# Exp_Board_Printrboard_v0_1.net
KiCad netlist of a schematic drawn in EAGLE
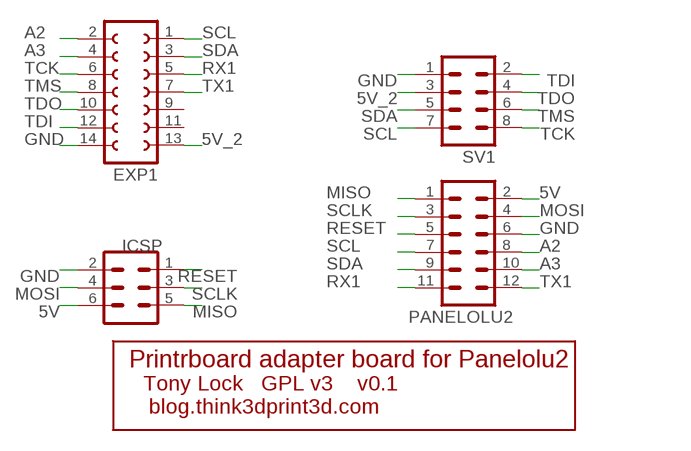
[diagram p0: schematic, sheet 1]

(export (version "E")
  (design (tool "Eeschema 10.0.6"))
  (components
    (comp (ref "EXP1")
      (value "FE07-2")
      (footprint "eagle-import:FE07-2")
      (libsource (lib "eagle-import") (part "FE07-2"))
    )
    (comp (ref "ICSP")
      (value "MA03-2")
      (footprint "eagle-import:MA03-2")
      (libsource (lib "eagle-import") (part "MA03-2"))
    )
    (comp (ref "PANELOLU2")
      (value "MA06-2_BACK")
      (footprint "eagle-import:MA06-2_BACK")
      (libsource (lib "eagle-import") (part "MA06-2_BACK"))
    )
    (comp (ref "SV1")
      (value "MA04-2")
      (footprint "eagle-import:MA04-2")
      (libsource (lib "eagle-import") (part "MA04-2"))
    )
  )
  (nets
    (net (code "1") (name "/5V") (class "Default")
      (node (ref "ICSP") (pin "6") (pinfunction "6_6") (pintype "passive"))
      (node (ref "PANELOLU2") (pin "2") (pinfunction "2_2") (pintype "passive"))
    )
    (net (code "2") (name "/5V_2") (class "Default")
      (node (ref "EXP1") (pin "13") (pinfunction "13_13") (pintype "passive"))
      (node (ref "SV1") (pin "3") (pinfunction "3_3") (pintype "passive"))
    )
    (net (code "3") (name "/A2") (class "Default")
      (node (ref "EXP1") (pin "2") (pinfunction "2_2") (pintype "passive"))
      (node (ref "PANELOLU2") (pin "8") (pinfunction "8_8") (pintype "passive"))
    )
    (net (code "4") (name "/A3") (class "Default")
      (node (ref "EXP1") (pin "4") (pinfunction "4_4") (pintype "passive"))
      (node (ref "PANELOLU2") (pin "10") (pinfunction "10_10") (pintype "passive"))
    )
    (net (code "5") (name "/GND") (class "Default")
      (node (ref "EXP1") (pin "14") (pinfunction "14_14") (pintype "passive"))
      (node (ref "ICSP") (pin "2") (pinfunction "2_2") (pintype "passive"))
      (node (ref "PANELOLU2") (pin "6") (pinfunction "6_6") (pintype "passive"))
      (node (ref "SV1") (pin "1") (pinfunction "1_1") (pintype "passive"))
    )
    (net (code "6") (name "/MISO") (class "Default")
      (node (ref "ICSP") (pin "5") (pinfunction "5_5") (pintype "passive"))
      (node (ref "PANELOLU2") (pin "1") (pinfunction "1_1") (pintype "passive"))
    )
    (net (code "7") (name "/MOSI") (class "Default")
      (node (ref "ICSP") (pin "4") (pinfunction "4_4") (pintype "passive"))
      (node (ref "PANELOLU2") (pin "4") (pinfunction "4_4") (pintype "passive"))
    )
    (net (code "8") (name "/RESET") (class "Default")
      (node (ref "ICSP") (pin "1") (pinfunction "1_1") (pintype "passive"))
      (node (ref "PANELOLU2") (pin "5") (pinfunction "5_5") (pintype "passive"))
    )
    (net (code "9") (name "/RX1") (class "Default")
      (node (ref "EXP1") (pin "5") (pinfunction "5_5") (pintype "passive"))
      (node (ref "PANELOLU2") (pin "11") (pinfunction "11_11") (pintype "passive"))
    )
    (net (code "10") (name "/SCL") (class "Default")
      (node (ref "EXP1") (pin "1") (pinfunction "1_1") (pintype "passive"))
      (node (ref "PANELOLU2") (pin "7") (pinfunction "7_7") (pintype "passive"))
      (node (ref "SV1") (pin "7") (pinfunction "7_7") (pintype "passive"))
    )
    (net (code "11") (name "/SCLK") (class "Default")
      (node (ref "ICSP") (pin "3") (pinfunction "3_3") (pintype "passive"))
      (node (ref "PANELOLU2") (pin "3") (pinfunction "3_3") (pintype "passive"))
    )
    (net (code "12") (name "/SDA") (class "Default")
      (node (ref "EXP1") (pin "3") (pinfunction "3_3") (pintype "passive"))
      (node (ref "PANELOLU2") (pin "9") (pinfunction "9_9") (pintype "passive"))
      (node (ref "SV1") (pin "5") (pinfunction "5_5") (pintype "passive"))
    )
    (net (code "13") (name "/TCK") (class "Default")
      (node (ref "EXP1") (pin "6") (pinfunction "6_6") (pintype "passive"))
      (node (ref "SV1") (pin "8") (pinfunction "8_8") (pintype "passive"))
    )
    (net (code "14") (name "/TDI") (class "Default")
      (node (ref "EXP1") (pin "12") (pinfunction "12_12") (pintype "passive"))
      (node (ref "SV1") (pin "2") (pinfunction "2_2") (pintype "passive"))
    )
    (net (code "15") (name "/TDO") (class "Default")
      (node (ref "EXP1") (pin "10") (pinfunction "10_10") (pintype "passive"))
      (node (ref "SV1") (pin "4") (pinfunction "4_4") (pintype "passive"))
    )
    (net (code "16") (name "/TMS") (class "Default")
      (node (ref "EXP1") (pin "8") (pinfunction "8_8") (pintype "passive"))
      (node (ref "SV1") (pin "6") (pinfunction "6_6") (pintype "passive"))
    )
    (net (code "17") (name "/TX1") (class "Default")
      (node (ref "EXP1") (pin "7") (pinfunction "7_7") (pintype "passive"))
      (node (ref "PANELOLU2") (pin "12") (pinfunction "12_12") (pintype "passive"))
    )
    (net (code "18") (name "unconnected-(EXP1-Pad9)") (class "Default")
      (node (ref "EXP1") (pin "9") (pinfunction "9_9") (pintype "passive"))
    )
    (net (code "19") (name "unconnected-(EXP1-Pad11)") (class "Default")
      (node (ref "EXP1") (pin "11") (pinfunction "11_11") (pintype "passive"))
    )
  )
)
